# MA600_Breakout.net
KiCad netlist of a schematic drawn in Altium Designer
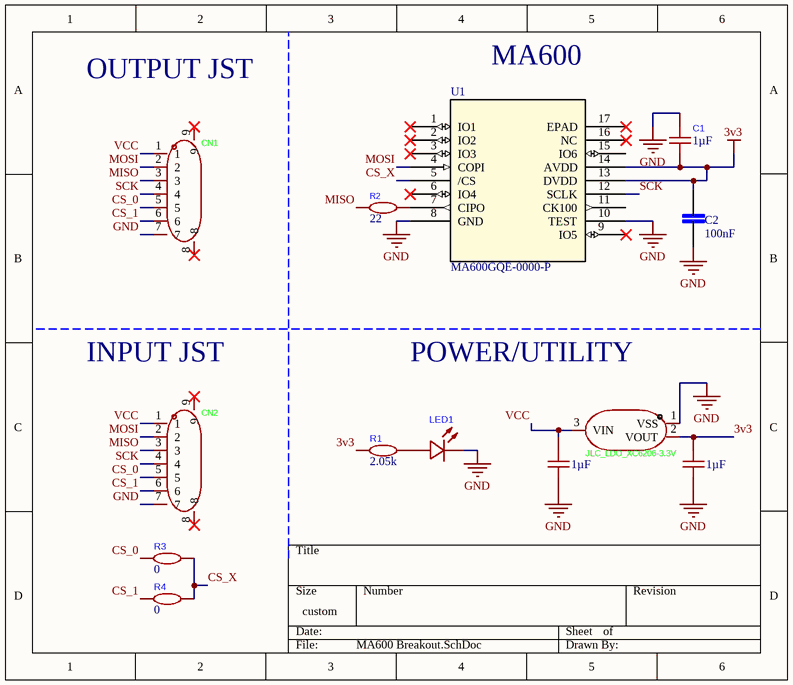
[diagram p0: MA600 Breakout.SchDoc]

(export (version "E")
  (design (tool "Eeschema 10.0.6"))
  (components
    (comp (ref "C1")
      (value "1µF")
      (footprint "C0603")
      (fields
        (field (name "MANUFACTURER PART") "CL10A105KB8NNNC")
        (field (name "TOLERANCE") "10%")
        (field (name "MANUFACTURER") "SAMSUNG(三星)")
      )
      (libsource (lib "CuPI Hexapod") (part "CL10A105KB8NNNC"))
    )
    (comp (ref "C2")
      (value "100nF")
      (footprint "CAPC1608X90")
      (description "0.1 ÂµF Â±10% 50V Ceramic Capacitor X7R 0603 (1608 Metric)")
      (fields (field (name "MP") "C0603C104K5RACTU") (field (name "MF") "KEMET"))
      (libsource (lib "CuPI Hexapod") (part "C0603C104K5RACTU"))
    )
    (comp (ref "C3")
      (value "1µF")
      (footprint "C0402")
      (description "1uF 25V X5R ±10% 0402 Multilayer Ceramic Capacitors MLCC - SMD/SMT ROHS")
      (fields
        (field (name "MANUFACTURER PART") "CL05A105KA5NQNC")
        (field (name "MANUFACTURER") "SAMSUNG(三星)")
      )
      (libsource (lib "CuPI Hexapod") (part "JLC_1uF_0402_CL05A105KA5NQNC"))
    )
    (comp (ref "C4")
      (value "1µF")
      (footprint "C0402")
      (description "1uF 25V X5R ±10% 0402 Multilayer Ceramic Capacitors MLCC - SMD/SMT ROHS")
      (fields
        (field (name "MANUFACTURER PART") "CL05A105KA5NQNC")
        (field (name "MANUFACTURER") "SAMSUNG(三星)")
      )
      (libsource (lib "CuPI Hexapod") (part "JLC_1uF_0402_CL05A105KA5NQNC"))
    )
    (comp (ref "CN1")
      (value "JLC_7P_TOP_ENTRY_BM07B-GHS-TBT(LF)(SN)(N)")
      (footprint "CONN-SMD_7P-P1.25_BM07B-GHS-TBT-LF-SN-N")
      (fields
        (field (name "MANUFACTURER PART") "BM07B-GHS-TBT(LF)(SN)(N)")
        (field (name "MANUFACTURER") "JST")
      )
      (libsource (lib "CuPI Hexapod") (part "JLC_7P_TOP_ENTRY_BM07B-GHS-TBT(LF)(SN)(N)"))
    )
    (comp (ref "CN2")
      (value "JLC_7P_TOP_ENTRY_BM07B-GHS-TBT(LF)(SN)(N)")
      (footprint "CONN-SMD_7P-P1.25_BM07B-GHS-TBT-LF-SN-N")
      (fields
        (field (name "MANUFACTURER PART") "BM07B-GHS-TBT(LF)(SN)(N)")
        (field (name "MANUFACTURER") "JST")
      )
      (libsource (lib "CuPI Hexapod") (part "JLC_7P_TOP_ENTRY_BM07B-GHS-TBT(LF)(SN)(N)"))
    )
    (comp (ref "LED1")
      (value "BLUE_LED_JLC_KT-0603B")
      (footprint "LED0603-RD")
      (description "100mW 120° 175mcd 3.1V 460nm~475nm 469nm 5mA Blue Water Clear 0603 LED Indication - Discrete ROHS")
      (fields (field (name "MANUFACTURER") "KENTO") (field (name "MANUFACTURER PART") "KT-0603B"))
      (libsource (lib "CuPI Hexapod") (part "BLUE_LED_JLC_KT-0603B"))
    )
    (comp (ref "R1")
      (value "2.05k")
      (footprint "R0603")
      (fields
        (field (name "MANUFACTURER PART") "0603WAF2051T5E")
        (field (name "MANUFACTURER") "UNI-ROYAL(厚声)")
        (field (name "TOLERANCE") "1%")
      )
      (libsource (lib "CuPI Hexapod") (part "JLC_0603WAF2051T5E"))
    )
    (comp (ref "R2")
      (value "22")
      (footprint "R0402")
      (fields
        (field (name "TOLERANCE") "1%")
        (field (name "MANUFACTURER") "UNI-ROYAL(厚声)")
        (field (name "MANUFACTURER PART") "0402WGF220JTCE")
      )
      (libsource (lib "CuPI Hexapod") (part "0402WGF220JTCE"))
    )
    (comp (ref "R3")
      (value "0")
      (footprint "R0603")
      (fields
        (field (name "MANUFACTURER") "UNI-ROYAL(厚声)")
        (field (name "MANUFACTURER PART") "0603WAJ0000T5E")
        (field (name "TOLERANCE") "5%")
      )
      (libsource (lib "CuPI Hexapod") (part "0 ohm_JLC_0603WAJ0000T5E"))
    )
    (comp (ref "R4")
      (value "0")
      (footprint "R0603")
      (fields
        (field (name "MANUFACTURER") "UNI-ROYAL(厚声)")
        (field (name "MANUFACTURER PART") "0603WAJ0000T5E")
        (field (name "TOLERANCE") "5%")
      )
      (libsource (lib "CuPI Hexapod") (part "0 ohm_JLC_0603WAJ0000T5E"))
    )
    (comp (ref "U1")
      (value "MA600GQE-0000-P")
      (footprint "QFN-16_MA600_MNP")
      (description "QFN-16-EP(3x3) Magnetic Angle Sensors ROHS")
      (fields
        (field (name "COPYRIGHT") "Copyright (C) 2025 Ultra Librarian. All rights reserved.")
        (field (name "SOURCE") "MA600GQE-0000-P_edited.SchLib")
      )
      (libsource (lib "CuPI Hexapod") (part "MA600GQE-0000-P"))
    )
    (comp (ref "U2")
      (value "JLC_LDO_XC6206-3.3V")
      (footprint "SOT-23-3_L2.9-W1.3-P0.95-LS2.4-BR")
      (fields (field (name "MANUFACTURER") "YONGYUTAI(永裕泰)") (field (name "MANUFACTURER PART") "XC6206-3.3V"))
      (libsource (lib "CuPI Hexapod") (part "JLC_LDO_XC6206-3.3V"))
    )
  )
  (nets
    (net (code "1") (name "/CS_0") (class "Default")
      (node (ref "CN1") (pin "5") (pinfunction "5_5") (pintype "passive"))
      (node (ref "CN2") (pin "5") (pinfunction "5_5") (pintype "passive"))
      (node (ref "R3") (pin "1") (pinfunction "1_1") (pintype "passive"))
    )
    (net (code "2") (name "/CS_1") (class "Default")
      (node (ref "CN1") (pin "6") (pinfunction "6_6") (pintype "passive"))
      (node (ref "CN2") (pin "6") (pinfunction "6_6") (pintype "passive"))
      (node (ref "R4") (pin "1") (pinfunction "1_1") (pintype "passive"))
    )
    (net (code "3") (name "/CS_X") (class "Default")
      (node (ref "R3") (pin "2") (pinfunction "2_2") (pintype "passive"))
      (node (ref "R4") (pin "2") (pinfunction "2_2") (pintype "passive"))
      (node (ref "U1") (pin "5") (pinfunction "/CS_5") (pintype "passive"))
    )
    (net (code "4") (name "/MISO") (class "Default")
      (node (ref "CN1") (pin "3") (pinfunction "3_3") (pintype "passive"))
      (node (ref "CN2") (pin "3") (pinfunction "3_3") (pintype "passive"))
      (node (ref "R2") (pin "1") (pinfunction "1_1") (pintype "passive"))
    )
    (net (code "5") (name "/MOSI") (class "Default")
      (node (ref "CN1") (pin "2") (pinfunction "2_2") (pintype "passive"))
      (node (ref "CN2") (pin "2") (pinfunction "2_2") (pintype "passive"))
      (node (ref "U1") (pin "4") (pinfunction "COPI_4") (pintype "input"))
    )
    (net (code "6") (name "/SCK") (class "Default")
      (node (ref "CN1") (pin "4") (pinfunction "4_4") (pintype "passive"))
      (node (ref "CN2") (pin "4") (pinfunction "4_4") (pintype "passive"))
      (node (ref "U1") (pin "12") (pinfunction "SCLK_12") (pintype "passive"))
    )
    (net (code "7") (name "/VCC") (class "Default")
      (node (ref "C4") (pin "2") (pinfunction "2_2") (pintype "passive"))
      (node (ref "CN1") (pin "1") (pinfunction "1_1") (pintype "passive"))
      (node (ref "CN2") (pin "1") (pinfunction "1_1") (pintype "passive"))
      (node (ref "U2") (pin "3") (pinfunction "VIN_3") (pintype "passive"))
    )
    (net (code "8") (name "3v3") (class "Default")
      (node (ref "C1") (pin "1") (pinfunction "1_1") (pintype "passive"))
      (node (ref "C2") (pin "1") (pinfunction "1_1") (pintype "passive"))
      (node (ref "C3") (pin "2") (pinfunction "2_2") (pintype "passive"))
      (node (ref "R1") (pin "1") (pinfunction "1_1") (pintype "passive"))
      (node (ref "U1") (pin "13") (pinfunction "DVDD_13") (pintype "power_in"))
      (node (ref "U1") (pin "14") (pinfunction "AVDD_14") (pintype "power_in"))
      (node (ref "U2") (pin "2") (pinfunction "VOUT_2") (pintype "passive"))
    )
    (net (code "9") (name "GND") (class "Default")
      (node (ref "C1") (pin "2") (pinfunction "2_2") (pintype "passive"))
      (node (ref "C2") (pin "2") (pinfunction "2_2") (pintype "passive"))
      (node (ref "C3") (pin "1") (pinfunction "1_1") (pintype "passive"))
      (node (ref "C4") (pin "1") (pinfunction "1_1") (pintype "passive"))
      (node (ref "CN1") (pin "7") (pinfunction "7_7") (pintype "passive"))
      (node (ref "CN2") (pin "7") (pinfunction "7_7") (pintype "passive"))
      (node (ref "LED1") (pin "1") (pinfunction "K_1") (pintype "passive"))
      (node (ref "U1") (pin "10") (pinfunction "TEST_10") (pintype "passive"))
      (node (ref "U1") (pin "8") (pinfunction "GND_8") (pintype "power_in"))
      (node (ref "U2") (pin "1") (pinfunction "VSS_1") (pintype "passive"))
    )
    (net (code "10") (name "Net-(LED1-A)") (class "Default")
      (node (ref "LED1") (pin "2") (pinfunction "A_2") (pintype "passive"))
      (node (ref "R1") (pin "2") (pinfunction "2_2") (pintype "passive"))
    )
    (net (code "11") (name "Net-(U1-CIPO)") (class "Default")
      (node (ref "R2") (pin "2") (pinfunction "2_2") (pintype "passive"))
      (node (ref "U1") (pin "7") (pinfunction "CIPO_7") (pintype "output"))
    )
    (net (code "12") (name "unconnected-(CN1-Pad8)") (class "Default")
      (node (ref "CN1") (pin "8") (pinfunction "8_8") (pintype "passive+no_connect"))
    )
    (net (code "13") (name "unconnected-(CN1-Pad9)") (class "Default")
      (node (ref "CN1") (pin "9") (pinfunction "9_9") (pintype "passive+no_connect"))
    )
    (net (code "14") (name "unconnected-(CN2-Pad8)") (class "Default")
      (node (ref "CN2") (pin "8") (pinfunction "8_8") (pintype "passive+no_connect"))
    )
    (net (code "15") (name "unconnected-(CN2-Pad9)") (class "Default")
      (node (ref "CN2") (pin "9") (pinfunction "9_9") (pintype "passive+no_connect"))
    )
    (net (code "16") (name "unconnected-(U1-CK100-Pad11)") (class "Default")
      (node (ref "U1") (pin "11") (pinfunction "CK100_11") (pintype "output"))
    )
    (net (code "17") (name "unconnected-(U1-EPAD-Pad17)") (class "Default")
      (node (ref "U1") (pin "17") (pinfunction "EPAD_17") (pintype "power_in+no_connect"))
    )
    (net (code "18") (name "unconnected-(U1-IO1-Pad1)") (class "Default")
      (node (ref "U1") (pin "1") (pinfunction "IO1_1") (pintype "bidirectional+no_connect"))
    )
    (net (code "19") (name "unconnected-(U1-IO2-Pad2)") (class "Default")
      (node (ref "U1") (pin "2") (pinfunction "IO2_2") (pintype "bidirectional+no_connect"))
    )
    (net (code "20") (name "unconnected-(U1-IO3-Pad3)") (class "Default")
      (node (ref "U1") (pin "3") (pinfunction "IO3_3") (pintype "bidirectional+no_connect"))
    )
    (net (code "21") (name "unconnected-(U1-IO4-Pad6)") (class "Default")
      (node (ref "U1") (pin "6") (pinfunction "IO4_6") (pintype "bidirectional+no_connect"))
    )
    (net (code "22") (name "unconnected-(U1-IO5-Pad9)") (class "Default")
      (node (ref "U1") (pin "9") (pinfunction "IO5_9") (pintype "bidirectional+no_connect"))
    )
    (net (code "23") (name "unconnected-(U1-IO6-Pad15)") (class "Default")
      (node (ref "U1") (pin "15") (pinfunction "IO6_15") (pintype "bidirectional"))
    )
    (net (code "24") (name "unconnected-(U1-NC-Pad16)") (class "Default")
      (node (ref "U1") (pin "16") (pinfunction "NC_16") (pintype "passive+no_connect"))
    )
  )
)
